# receiver.net
KiCad netlist of a schematic drawn in EAGLE
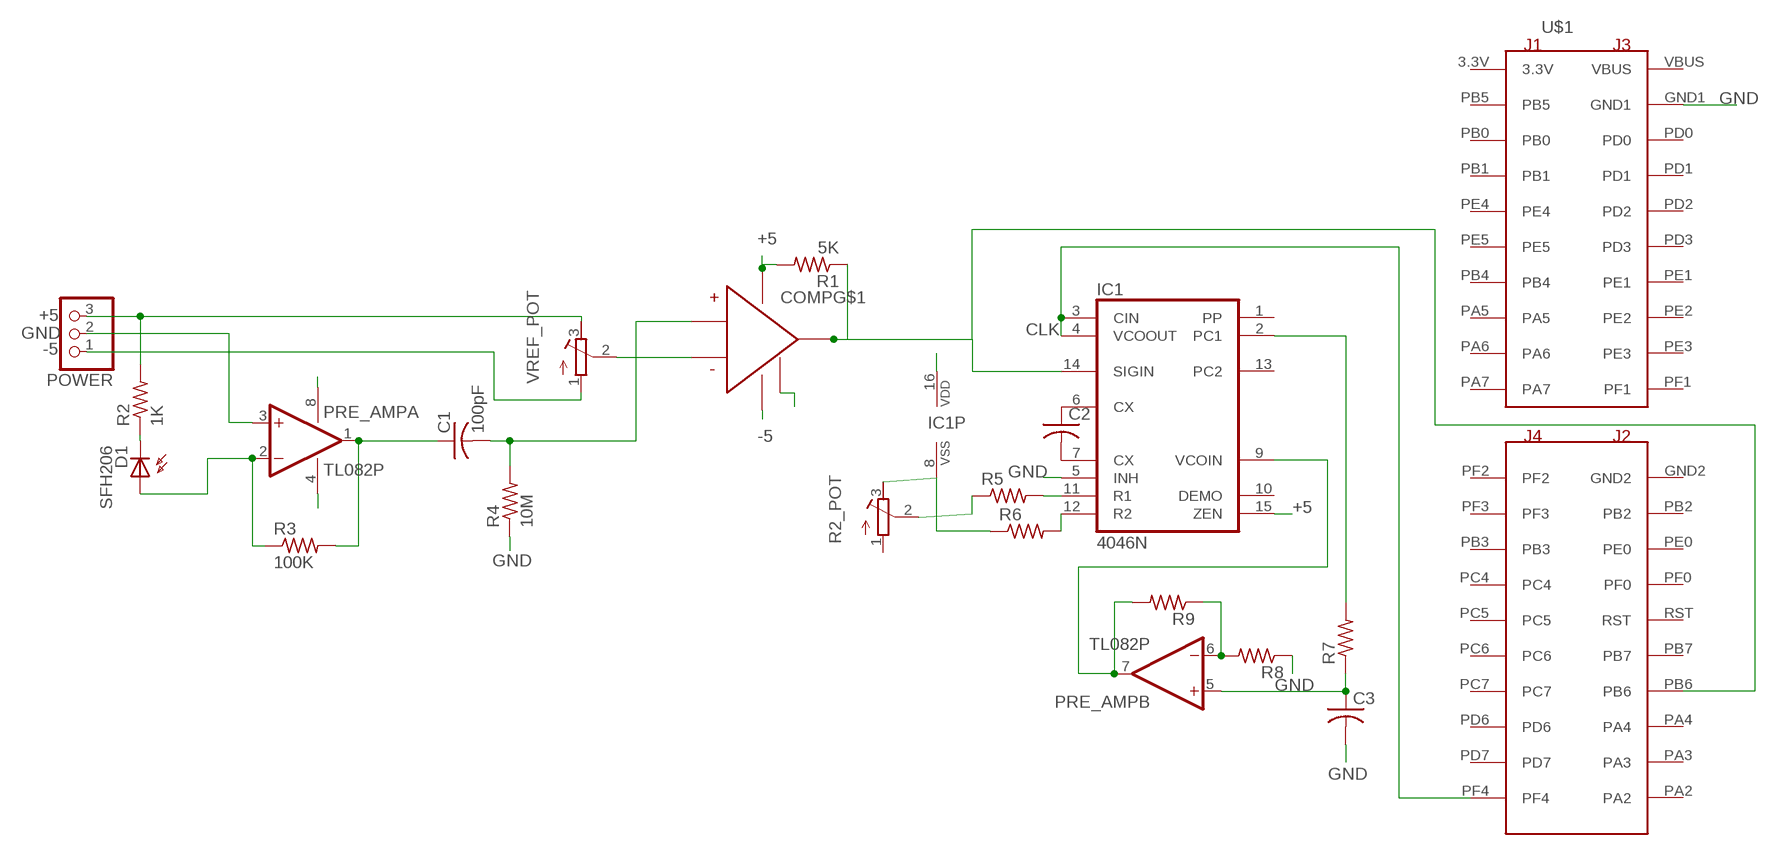
[diagram p0: schematic, sheet 1]

(export (version "E")
  (design (tool "Eeschema 10.0.6"))
  (components
    (comp (ref "C1")
      (value "100pF")
      (footprint "eagle-import:C050-025X075")
      (libsource (lib "eagle-import") (part "C-US050-025X075"))
    )
    (comp (ref "C2")
      (value "C-US050-025X075")
      (footprint "eagle-import:C050-025X075")
      (libsource (lib "eagle-import") (part "C-US050-025X075"))
    )
    (comp (ref "C3")
      (value "C-US050-025X075")
      (footprint "eagle-import:C050-025X075")
      (libsource (lib "eagle-import") (part "C-US050-025X075"))
    )
    (comp (ref "COMP")
      (value "LM319")
      (footprint "eagle-import:DIL14-1")
      (libsource (lib "eagle-import") (part "LM319"))
    )
    (comp (ref "D1")
      (value "SFH206")
      (footprint "eagle-import:SFH206")
      (fields (field (name "MPN") "SFH206K"))
      (libsource (lib "eagle-import") (part "SFH206"))
    )
    (comp (ref "IC1")
      (value "4046N")
      (footprint "eagle-import:DIL16")
      (libsource (lib "eagle-import") (part "4046N"))
    )
    (comp (ref "POWER")
      (value "PINHD-1X3")
      (footprint "eagle-import:1X03")
      (libsource (lib "eagle-import") (part "PINHD-1X3"))
    )
    (comp (ref "PRE_AMP")
      (value "TL082P")
      (footprint "eagle-import:DIL08")
      (libsource (lib "eagle-import") (part "TL082P"))
    )
    (comp (ref "R1")
      (value "5K")
      (footprint "eagle-import:0207_10")
      (libsource (lib "eagle-import") (part "resistor_R-US_0207/10"))
    )
    (comp (ref "R2")
      (value "1K")
      (footprint "eagle-import:0207_10")
      (libsource (lib "eagle-import") (part "R-US_0207/10"))
    )
    (comp (ref "R2_POT")
      (value "R-TRIMM3296Y")
      (footprint "eagle-import:RTRIM3296Y")
      (libsource (lib "eagle-import") (part "R-TRIMM3296Y"))
    )
    (comp (ref "R3")
      (value "100K")
      (footprint "eagle-import:0207_10")
      (libsource (lib "eagle-import") (part "R-US_0207/10"))
    )
    (comp (ref "R4")
      (value "10M")
      (footprint "eagle-import:0207_10")
      (libsource (lib "eagle-import") (part "R-US_0207/10"))
    )
    (comp (ref "R5")
      (value "R-US_0207/10")
      (footprint "eagle-import:0207_10")
      (libsource (lib "eagle-import") (part "resistor_R-US_0207/10"))
    )
    (comp (ref "R6")
      (value "R-US_0207/10")
      (footprint "eagle-import:0207_10")
      (libsource (lib "eagle-import") (part "resistor_R-US_0207/10"))
    )
    (comp (ref "R7")
      (value "R-US_0207/10")
      (footprint "eagle-import:0207_10")
      (libsource (lib "eagle-import") (part "resistor_R-US_0207/10"))
    )
    (comp (ref "R8")
      (value "R-US_0207/10")
      (footprint "eagle-import:0207_10")
      (libsource (lib "eagle-import") (part "resistor_R-US_0207/10"))
    )
    (comp (ref "R9")
      (value "R-US_0207/10")
      (footprint "eagle-import:0207_10")
      (libsource (lib "eagle-import") (part "resistor_R-US_0207/10"))
    )
    (comp (ref "U$1")
      (value "STELLARIS_LAUNCHPAD_BLIZZARD_XL_HEADERS")
      (footprint "eagle-import:STELLARISLAUNCHPADHEADERS")
      (libsource (lib "eagle-import") (part "STELLARIS_LAUNCHPAD_BLIZZARD_XL_HEADERS"))
    )
    (comp (ref "VREF_POT")
      (value "R-TRIMM3296Y")
      (footprint "eagle-import:RTRIM3296Y")
      (libsource (lib "eagle-import") (part "R-TRIMM3296Y"))
    )
  )
  (nets
    (net (code "1") (name "/+5") (class "Default")
      (node (ref "COMP") (pin "P11") (pinfunction "VCC_P11") (pintype "bidirectional"))
      (node (ref "IC1") (pin "15") (pinfunction "ZEN_15") (pintype "input"))
      (node (ref "IC1") (pin "16") (pinfunction "VDD_16") (pintype "power_in"))
      (node (ref "POWER") (pin "3") (pinfunction "3_3") (pintype "passive"))
      (node (ref "PRE_AMP") (pin "8") (pinfunction "V+_8") (pintype "power_in"))
      (node (ref "R1") (pin "2") (pinfunction "2_2") (pintype "passive"))
      (node (ref "R2") (pin "2") (pinfunction "2_2") (pintype "passive"))
      (node (ref "VREF_POT") (pin "3") (pinfunction "E_3") (pintype "passive"))
    )
    (net (code "2") (name "/-5") (class "Default")
      (node (ref "COMP") (pin "P6") (pinfunction "GND_P6") (pintype "bidirectional"))
      (node (ref "POWER") (pin "1") (pinfunction "1_1") (pintype "passive"))
      (node (ref "PRE_AMP") (pin "4") (pinfunction "V-_4") (pintype "power_in"))
      (node (ref "VREF_POT") (pin "1") (pinfunction "A_1") (pintype "passive"))
    )
    (net (code "3") (name "/3.3V") (class "Default")
      (node (ref "U$1") (pin "3.3V") (pinfunction "3.3V_3.3V") (pintype "power_in"))
    )
    (net (code "4") (name "/CLK") (class "Default")
      (node (ref "IC1") (pin "3") (pinfunction "CIN_3") (pintype "input"))
      (node (ref "IC1") (pin "4") (pinfunction "VCOOUT_4") (pintype "output"))
      (node (ref "U$1") (pin "PF4") (pinfunction "PF4_PF4") (pintype "bidirectional"))
    )
    (net (code "5") (name "/GND") (class "Default")
      (node (ref "C3") (pin "2") (pinfunction "2_2") (pintype "passive"))
      (node (ref "COMP") (pin "P3") (pinfunction "GND2_P3") (pintype "bidirectional"))
      (node (ref "IC1") (pin "5") (pinfunction "INH_5") (pintype "input"))
      (node (ref "IC1") (pin "8") (pinfunction "VSS_8") (pintype "power_in"))
      (node (ref "POWER") (pin "2") (pinfunction "2_2") (pintype "passive"))
      (node (ref "PRE_AMP") (pin "3") (pinfunction "+IN_3") (pintype "input"))
      (node (ref "R2_POT") (pin "3") (pinfunction "E_3") (pintype "passive"))
      (node (ref "R4") (pin "1") (pinfunction "1_1") (pintype "passive"))
      (node (ref "R6") (pin "1") (pinfunction "1_1") (pintype "passive"))
      (node (ref "R8") (pin "1") (pinfunction "1_1") (pintype "passive"))
      (node (ref "U$1") (pin "GND1") (pinfunction "GND1_GND1") (pintype "bidirectional"))
    )
    (net (code "6") (name "/GND2") (class "Default")
      (node (ref "U$1") (pin "GND2") (pinfunction "GND2_GND2") (pintype "power_in"))
    )
    (net (code "7") (name "/RST") (class "Default")
      (node (ref "U$1") (pin "RST") (pinfunction "RST_RST") (pintype "power_in"))
    )
    (net (code "8") (name "/VBUS") (class "Default")
      (node (ref "U$1") (pin "VBUS") (pinfunction "VBUS_VBUS") (pintype "power_in"))
    )
    (net (code "9") (name "Net-(C2-Pad1)") (class "Default")
      (node (ref "C2") (pin "1") (pinfunction "1_1") (pintype "passive"))
      (node (ref "IC1") (pin "6") (pinfunction "CX_6") (pintype "input"))
    )
    (net (code "10") (name "Net-(C2-Pad2)") (class "Default")
      (node (ref "C2") (pin "2") (pinfunction "2_2") (pintype "passive"))
      (node (ref "IC1") (pin "7") (pinfunction "CX_7") (pintype "input"))
    )
    (net (code "11") (name "Net-(COMPA-INV)") (class "Default")
      (node (ref "COMP") (pin "P5") (pinfunction "INV_P5") (pintype "bidirectional"))
      (node (ref "VREF_POT") (pin "2") (pinfunction "S_2") (pintype "passive"))
    )
    (net (code "12") (name "Net-(COMPA-NONINV)") (class "Default")
      (node (ref "C1") (pin "2") (pinfunction "2_2") (pintype "passive"))
      (node (ref "COMP") (pin "P4") (pinfunction "NONINV_P4") (pintype "bidirectional"))
      (node (ref "R4") (pin "2") (pinfunction "2_2") (pintype "passive"))
    )
    (net (code "13") (name "Net-(COMPA-OUT)") (class "Default")
      (node (ref "COMP") (pin "P12") (pinfunction "OUT_P12") (pintype "bidirectional"))
      (node (ref "IC1") (pin "14") (pinfunction "SIGIN_14") (pintype "input"))
      (node (ref "R1") (pin "1") (pinfunction "1_1") (pintype "passive"))
      (node (ref "U$1") (pin "PB6") (pinfunction "PB6_PB6") (pintype "bidirectional"))
    )
    (net (code "14") (name "Net-(D1-C)") (class "Default")
      (node (ref "D1") (pin "K") (pinfunction "C_K") (pintype "passive"))
      (node (ref "R2") (pin "1") (pinfunction "1_1") (pintype "passive"))
    )
    (net (code "15") (name "Net-(IC1A-PC1)") (class "Default")
      (node (ref "IC1") (pin "2") (pinfunction "PC1_2") (pintype "output"))
      (node (ref "R7") (pin "2") (pinfunction "2_2") (pintype "passive"))
    )
    (net (code "16") (name "Net-(IC1A-R1)") (class "Default")
      (node (ref "IC1") (pin "11") (pinfunction "R1_11") (pintype "input"))
      (node (ref "R5") (pin "2") (pinfunction "2_2") (pintype "passive"))
    )
    (net (code "17") (name "Net-(IC1A-R2)") (class "Default")
      (node (ref "IC1") (pin "12") (pinfunction "R2_12") (pintype "input"))
      (node (ref "R6") (pin "2") (pinfunction "2_2") (pintype "passive"))
    )
    (net (code "18") (name "Net-(IC1A-VCOIN)") (class "Default")
      (node (ref "IC1") (pin "9") (pinfunction "VCOIN_9") (pintype "input"))
      (node (ref "PRE_AMP") (pin "7") (pinfunction "OUT_7") (pintype "output"))
      (node (ref "R9") (pin "2") (pinfunction "2_2") (pintype "passive"))
    )
    (net (code "19") (name "Net-(PRE_AMPA--IN)") (class "Default")
      (node (ref "D1") (pin "A") (pinfunction "A_A") (pintype "passive"))
      (node (ref "PRE_AMP") (pin "2") (pinfunction "-IN_2") (pintype "input"))
      (node (ref "R3") (pin "1") (pinfunction "1_1") (pintype "passive"))
    )
    (net (code "20") (name "Net-(PRE_AMPA-OUT)") (class "Default")
      (node (ref "C1") (pin "1") (pinfunction "1_1") (pintype "passive"))
      (node (ref "PRE_AMP") (pin "1") (pinfunction "OUT_1") (pintype "output"))
      (node (ref "R3") (pin "2") (pinfunction "2_2") (pintype "passive"))
    )
    (net (code "21") (name "Net-(PRE_AMPB-+IN)") (class "Default")
      (node (ref "C3") (pin "1") (pinfunction "1_1") (pintype "passive"))
      (node (ref "PRE_AMP") (pin "5") (pinfunction "+IN_5") (pintype "input"))
      (node (ref "R7") (pin "1") (pinfunction "1_1") (pintype "passive"))
    )
    (net (code "22") (name "Net-(PRE_AMPB--IN)") (class "Default")
      (node (ref "PRE_AMP") (pin "6") (pinfunction "-IN_6") (pintype "input"))
      (node (ref "R8") (pin "2") (pinfunction "2_2") (pintype "passive"))
      (node (ref "R9") (pin "1") (pinfunction "1_1") (pintype "passive"))
    )
    (net (code "23") (name "Net-(R2_POT-S)") (class "Default")
      (node (ref "R2_POT") (pin "2") (pinfunction "S_2") (pintype "passive"))
      (node (ref "R5") (pin "1") (pinfunction "1_1") (pintype "passive"))
    )
    (net (code "24") (name "unconnected-(IC1A-DEMO-Pad10)") (class "Default")
      (node (ref "IC1") (pin "10") (pinfunction "DEMO_10") (pintype "output"))
    )
    (net (code "25") (name "unconnected-(IC1A-PC2-Pad13)") (class "Default")
      (node (ref "IC1") (pin "13") (pinfunction "PC2_13") (pintype "output"))
    )
    (net (code "26") (name "unconnected-(IC1A-PP-Pad1)") (class "Default")
      (node (ref "IC1") (pin "1") (pinfunction "PP_1") (pintype "output"))
    )
    (net (code "27") (name "unconnected-(R2_POT-A-Pad1)") (class "Default")
      (node (ref "R2_POT") (pin "1") (pinfunction "A_1") (pintype "passive"))
    )
    (net (code "28") (name "unconnected-(U$1-PadPA2)") (class "Default")
      (node (ref "U$1") (pin "PA2") (pinfunction "PA2_PA2") (pintype "bidirectional"))
    )
    (net (code "29") (name "unconnected-(U$1-PadPA3)") (class "Default")
      (node (ref "U$1") (pin "PA3") (pinfunction "PA3_PA3") (pintype "bidirectional"))
    )
    (net (code "30") (name "unconnected-(U$1-PadPA4)") (class "Default")
      (node (ref "U$1") (pin "PA4") (pinfunction "PA4_PA4") (pintype "bidirectional"))
    )
    (net (code "31") (name "unconnected-(U$1-PadPA5)") (class "Default")
      (node (ref "U$1") (pin "PA5") (pinfunction "PA5_PA5") (pintype "bidirectional"))
    )
    (net (code "32") (name "unconnected-(U$1-PadPA6)") (class "Default")
      (node (ref "U$1") (pin "PA6") (pinfunction "PA6_PA6") (pintype "bidirectional"))
    )
    (net (code "33") (name "unconnected-(U$1-PadPA7)") (class "Default")
      (node (ref "U$1") (pin "PA7") (pinfunction "PA7_PA7") (pintype "bidirectional"))
    )
    (net (code "34") (name "unconnected-(U$1-PadPB0)") (class "Default")
      (node (ref "U$1") (pin "PB0") (pinfunction "PB0_PB0") (pintype "bidirectional"))
    )
    (net (code "35") (name "unconnected-(U$1-PadPB1)") (class "Default")
      (node (ref "U$1") (pin "PB1") (pinfunction "PB1_PB1") (pintype "bidirectional"))
    )
    (net (code "36") (name "unconnected-(U$1-PadPB2)") (class "Default")
      (node (ref "U$1") (pin "PB2") (pinfunction "PB2_PB2") (pintype "bidirectional"))
    )
    (net (code "37") (name "unconnected-(U$1-PadPB3)") (class "Default")
      (node (ref "U$1") (pin "PB3") (pinfunction "PB3_PB3") (pintype "bidirectional"))
    )
    (net (code "38") (name "unconnected-(U$1-PadPB4)") (class "Default")
      (node (ref "U$1") (pin "PB4") (pinfunction "PB4_PB4") (pintype "bidirectional"))
    )
    (net (code "39") (name "unconnected-(U$1-PadPB5)") (class "Default")
      (node (ref "U$1") (pin "PB5") (pinfunction "PB5_PB5") (pintype "bidirectional"))
    )
    (net (code "40") (name "unconnected-(U$1-PadPB7)") (class "Default")
      (node (ref "U$1") (pin "PB7") (pinfunction "PB7_PB7") (pintype "bidirectional"))
    )
    (net (code "41") (name "unconnected-(U$1-PadPC4)") (class "Default")
      (node (ref "U$1") (pin "PC4") (pinfunction "PC4_PC4") (pintype "bidirectional"))
    )
    (net (code "42") (name "unconnected-(U$1-PadPC5)") (class "Default")
      (node (ref "U$1") (pin "PC5") (pinfunction "PC5_PC5") (pintype "bidirectional"))
    )
    (net (code "43") (name "unconnected-(U$1-PadPC6)") (class "Default")
      (node (ref "U$1") (pin "PC6") (pinfunction "PC6_PC6") (pintype "bidirectional"))
    )
    (net (code "44") (name "unconnected-(U$1-PadPC7)") (class "Default")
      (node (ref "U$1") (pin "PC7") (pinfunction "PC7_PC7") (pintype "bidirectional"))
    )
    (net (code "45") (name "unconnected-(U$1-PadPD0)") (class "Default")
      (node (ref "U$1") (pin "PD0") (pinfunction "PD0_PD0") (pintype "bidirectional"))
    )
    (net (code "46") (name "unconnected-(U$1-PadPD1)") (class "Default")
      (node (ref "U$1") (pin "PD1") (pinfunction "PD1_PD1") (pintype "bidirectional"))
    )
    (net (code "47") (name "unconnected-(U$1-PadPD2)") (class "Default")
      (node (ref "U$1") (pin "PD2") (pinfunction "PD2_PD2") (pintype "bidirectional"))
    )
    (net (code "48") (name "unconnected-(U$1-PadPD3)") (class "Default")
      (node (ref "U$1") (pin "PD3") (pinfunction "PD3_PD3") (pintype "bidirectional"))
    )
    (net (code "49") (name "unconnected-(U$1-PadPD6)") (class "Default")
      (node (ref "U$1") (pin "PD6") (pinfunction "PD6_PD6") (pintype "bidirectional"))
    )
    (net (code "50") (name "unconnected-(U$1-PadPD7)") (class "Default")
      (node (ref "U$1") (pin "PD7") (pinfunction "PD7_PD7") (pintype "bidirectional"))
    )
    (net (code "51") (name "unconnected-(U$1-PadPE0)") (class "Default")
      (node (ref "U$1") (pin "PE0") (pinfunction "PE0_PE0") (pintype "bidirectional"))
    )
    (net (code "52") (name "unconnected-(U$1-PadPE1)") (class "Default")
      (node (ref "U$1") (pin "PE1") (pinfunction "PE1_PE1") (pintype "bidirectional"))
    )
    (net (code "53") (name "unconnected-(U$1-PadPE2)") (class "Default")
      (node (ref "U$1") (pin "PE2") (pinfunction "PE2_PE2") (pintype "bidirectional"))
    )
    (net (code "54") (name "unconnected-(U$1-PadPE3)") (class "Default")
      (node (ref "U$1") (pin "PE3") (pinfunction "PE3_PE3") (pintype "bidirectional"))
    )
    (net (code "55") (name "unconnected-(U$1-PadPE4)") (class "Default")
      (node (ref "U$1") (pin "PE4") (pinfunction "PE4_PE4") (pintype "bidirectional"))
    )
    (net (code "56") (name "unconnected-(U$1-PadPE5)") (class "Default")
      (node (ref "U$1") (pin "PE5") (pinfunction "PE5_PE5") (pintype "bidirectional"))
    )
    (net (code "57") (name "unconnected-(U$1-PadPF0)") (class "Default")
      (node (ref "U$1") (pin "PF0") (pinfunction "PF0_PF0") (pintype "bidirectional"))
    )
    (net (code "58") (name "unconnected-(U$1-PadPF1)") (class "Default")
      (node (ref "U$1") (pin "PF1") (pinfunction "PF1_PF1") (pintype "bidirectional"))
    )
    (net (code "59") (name "unconnected-(U$1-PadPF2)") (class "Default")
      (node (ref "U$1") (pin "PF2") (pinfunction "PF2_PF2") (pintype "bidirectional"))
    )
    (net (code "60") (name "unconnected-(U$1-PadPF3)") (class "Default")
      (node (ref "U$1") (pin "PF3") (pinfunction "PF3_PF3") (pintype "bidirectional"))
    )
  )
)
